# WRTnode.net
KiCad netlist of a schematic drawn in Altium Designer
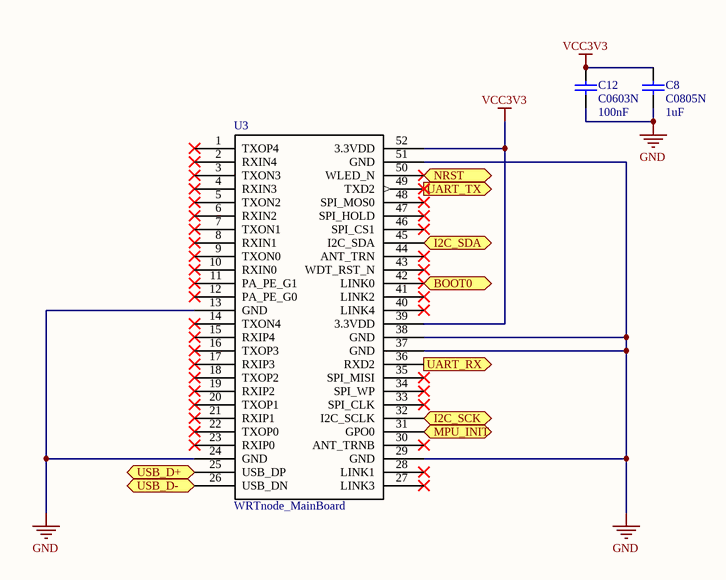
[diagram p0: WRTnode.SchDoc]

(export (version "E")
  (design (tool "Eeschema 10.0.6"))
  (components
    (comp (ref "C8")
      (value "C0805N")
      (footprint "C0805N")
      (description "Capacitor")
      (fields (field (name "ALTIUM_VALUE") "1uF") (field (name "PUBLISHER") "Altium Limited"))
      (libsource (lib "Miscellaneous Devices") (part "Cap"))
    )
    (comp (ref "C12")
      (value "C0603N")
      (footprint "C0603N")
      (description "Capacitor")
      (fields (field (name "ALTIUM_VALUE") "100nF") (field (name "PUBLISHER") "Altium Limited"))
      (libsource (lib "Miscellaneous Devices") (part "Cap"))
    )
    (comp (ref "U3")
      (value "WRTnode_MainBoard")
      (footprint "schumyhao's_IC:WRTnode_MainBoard_DIP26*2")
      (libsource (lib "schumyhao's_IC") (part "WRTnode_MainBoard"))
    )
  )
  (nets
    (net (code "1") (name "/BOOT0") (class "Default")
      (node (ref "U3") (pin "42") (pinfunction "LINK0_42") (pintype "passive+no_connect"))
    )
    (net (code "2") (name "/I2C_SCK") (class "Default")
      (node (ref "U3") (pin "32") (pinfunction "I2C_SCLK_32") (pintype "passive"))
    )
    (net (code "3") (name "/I2C_SDA") (class "Default")
      (node (ref "U3") (pin "45") (pinfunction "I2C_SDA_45") (pintype "passive"))
    )
    (net (code "4") (name "/MPU_INIT") (class "Default")
      (node (ref "U3") (pin "31") (pinfunction "GPO0_31") (pintype "passive"))
    )
    (net (code "5") (name "/NRST") (class "Default")
      (node (ref "U3") (pin "50") (pinfunction "WLED_N_50") (pintype "passive+no_connect"))
    )
    (net (code "6") (name "/UART_RX") (class "Default")
      (node (ref "U3") (pin "36") (pinfunction "RXD2_36") (pintype "passive"))
    )
    (net (code "7") (name "/UART_TX") (class "Default")
      (node (ref "U3") (pin "49") (pinfunction "TXD2_49") (pintype "output+no_connect"))
    )
    (net (code "8") (name "/USB_D+") (class "Default")
      (node (ref "U3") (pin "25") (pinfunction "USB_DP_25") (pintype "passive"))
    )
    (net (code "9") (name "/USB_D-") (class "Default")
      (node (ref "U3") (pin "26") (pinfunction "USB_DN_26") (pintype "passive"))
    )
    (net (code "10") (name "GND") (class "Default")
      (node (ref "C12") (pin "1") (pinfunction "1_1") (pintype "passive"))
      (node (ref "C8") (pin "1") (pinfunction "1_1") (pintype "passive"))
      (node (ref "U3") (pin "13") (pinfunction "GND_13") (pintype "passive"))
      (node (ref "U3") (pin "24") (pinfunction "GND_24") (pintype "passive"))
      (node (ref "U3") (pin "29") (pinfunction "GND_29") (pintype "passive"))
      (node (ref "U3") (pin "37") (pinfunction "GND_37") (pintype "passive"))
      (node (ref "U3") (pin "38") (pinfunction "GND_38") (pintype "passive"))
      (node (ref "U3") (pin "51") (pinfunction "GND_51") (pintype "passive"))
    )
    (net (code "11") (name "VCC3V3") (class "Default")
      (node (ref "C12") (pin "2") (pinfunction "2_2") (pintype "passive"))
      (node (ref "C8") (pin "2") (pinfunction "2_2") (pintype "passive"))
      (node (ref "U3") (pin "39") (pinfunction "3.3VDD_39") (pintype "passive"))
      (node (ref "U3") (pin "52") (pinfunction "3.3VDD_52") (pintype "passive"))
    )
    (net (code "12") (name "unconnected-(U3-ANT_TRN-Pad44)") (class "Default")
      (node (ref "U3") (pin "44") (pinfunction "ANT_TRN_44") (pintype "passive+no_connect"))
    )
    (net (code "13") (name "unconnected-(U3-ANT_TRNB-Pad30)") (class "Default")
      (node (ref "U3") (pin "30") (pinfunction "ANT_TRNB_30") (pintype "passive+no_connect"))
    )
    (net (code "14") (name "unconnected-(U3-LINK1-Pad28)") (class "Default")
      (node (ref "U3") (pin "28") (pinfunction "LINK1_28") (pintype "passive+no_connect"))
    )
    (net (code "15") (name "unconnected-(U3-LINK2-Pad41)") (class "Default")
      (node (ref "U3") (pin "41") (pinfunction "LINK2_41") (pintype "passive+no_connect"))
    )
    (net (code "16") (name "unconnected-(U3-LINK3-Pad27)") (class "Default")
      (node (ref "U3") (pin "27") (pinfunction "LINK3_27") (pintype "passive+no_connect"))
    )
    (net (code "17") (name "unconnected-(U3-LINK4-Pad40)") (class "Default")
      (node (ref "U3") (pin "40") (pinfunction "LINK4_40") (pintype "passive+no_connect"))
    )
    (net (code "18") (name "unconnected-(U3-PA_PE_G0-Pad12)") (class "Default")
      (node (ref "U3") (pin "12") (pinfunction "PA_PE_G0_12") (pintype "passive+no_connect"))
    )
    (net (code "19") (name "unconnected-(U3-PA_PE_G1-Pad11)") (class "Default")
      (node (ref "U3") (pin "11") (pinfunction "PA_PE_G1_11") (pintype "passive+no_connect"))
    )
    (net (code "20") (name "unconnected-(U3-RXIN0-Pad10)") (class "Default")
      (node (ref "U3") (pin "10") (pinfunction "RXIN0_10") (pintype "passive+no_connect"))
    )
    (net (code "21") (name "unconnected-(U3-RXIN1-Pad8)") (class "Default")
      (node (ref "U3") (pin "8") (pinfunction "RXIN1_8") (pintype "passive+no_connect"))
    )
    (net (code "22") (name "unconnected-(U3-RXIN2-Pad6)") (class "Default")
      (node (ref "U3") (pin "6") (pinfunction "RXIN2_6") (pintype "passive+no_connect"))
    )
    (net (code "23") (name "unconnected-(U3-RXIN3-Pad4)") (class "Default")
      (node (ref "U3") (pin "4") (pinfunction "RXIN3_4") (pintype "passive+no_connect"))
    )
    (net (code "24") (name "unconnected-(U3-RXIN4-Pad2)") (class "Default")
      (node (ref "U3") (pin "2") (pinfunction "RXIN4_2") (pintype "passive+no_connect"))
    )
    (net (code "25") (name "unconnected-(U3-RXIP0-Pad23)") (class "Default")
      (node (ref "U3") (pin "23") (pinfunction "RXIP0_23") (pintype "passive+no_connect"))
    )
    (net (code "26") (name "unconnected-(U3-RXIP1-Pad21)") (class "Default")
      (node (ref "U3") (pin "21") (pinfunction "RXIP1_21") (pintype "passive+no_connect"))
    )
    (net (code "27") (name "unconnected-(U3-RXIP2-Pad19)") (class "Default")
      (node (ref "U3") (pin "19") (pinfunction "RXIP2_19") (pintype "passive+no_connect"))
    )
    (net (code "28") (name "unconnected-(U3-RXIP3-Pad17)") (class "Default")
      (node (ref "U3") (pin "17") (pinfunction "RXIP3_17") (pintype "passive+no_connect"))
    )
    (net (code "29") (name "unconnected-(U3-RXIP4-Pad15)") (class "Default")
      (node (ref "U3") (pin "15") (pinfunction "RXIP4_15") (pintype "passive+no_connect"))
    )
    (net (code "30") (name "unconnected-(U3-SPI_CLK-Pad33)") (class "Default")
      (node (ref "U3") (pin "33") (pinfunction "SPI_CLK_33") (pintype "passive+no_connect"))
    )
    (net (code "31") (name "unconnected-(U3-SPI_CS1-Pad46)") (class "Default")
      (node (ref "U3") (pin "46") (pinfunction "SPI_CS1_46") (pintype "passive+no_connect"))
    )
    (net (code "32") (name "unconnected-(U3-SPI_HOLD-Pad47)") (class "Default")
      (node (ref "U3") (pin "47") (pinfunction "SPI_HOLD_47") (pintype "passive+no_connect"))
    )
    (net (code "33") (name "unconnected-(U3-SPI_MISI-Pad35)") (class "Default")
      (node (ref "U3") (pin "35") (pinfunction "SPI_MISI_35") (pintype "passive+no_connect"))
    )
    (net (code "34") (name "unconnected-(U3-SPI_MOS0-Pad48)") (class "Default")
      (node (ref "U3") (pin "48") (pinfunction "SPI_MOS0_48") (pintype "passive+no_connect"))
    )
    (net (code "35") (name "unconnected-(U3-SPI_WP-Pad34)") (class "Default")
      (node (ref "U3") (pin "34") (pinfunction "SPI_WP_34") (pintype "passive+no_connect"))
    )
    (net (code "36") (name "unconnected-(U3-TXON0-Pad9)") (class "Default")
      (node (ref "U3") (pin "9") (pinfunction "TXON0_9") (pintype "passive+no_connect"))
    )
    (net (code "37") (name "unconnected-(U3-TXON1-Pad7)") (class "Default")
      (node (ref "U3") (pin "7") (pinfunction "TXON1_7") (pintype "passive+no_connect"))
    )
    (net (code "38") (name "unconnected-(U3-TXON2-Pad5)") (class "Default")
      (node (ref "U3") (pin "5") (pinfunction "TXON2_5") (pintype "passive+no_connect"))
    )
    (net (code "39") (name "unconnected-(U3-TXON3-Pad3)") (class "Default")
      (node (ref "U3") (pin "3") (pinfunction "TXON3_3") (pintype "passive+no_connect"))
    )
    (net (code "40") (name "unconnected-(U3-TXON4-Pad14)") (class "Default")
      (node (ref "U3") (pin "14") (pinfunction "TXON4_14") (pintype "passive+no_connect"))
    )
    (net (code "41") (name "unconnected-(U3-TXOP0-Pad22)") (class "Default")
      (node (ref "U3") (pin "22") (pinfunction "TXOP0_22") (pintype "passive+no_connect"))
    )
    (net (code "42") (name "unconnected-(U3-TXOP1-Pad20)") (class "Default")
      (node (ref "U3") (pin "20") (pinfunction "TXOP1_20") (pintype "passive+no_connect"))
    )
    (net (code "43") (name "unconnected-(U3-TXOP2-Pad18)") (class "Default")
      (node (ref "U3") (pin "18") (pinfunction "TXOP2_18") (pintype "passive+no_connect"))
    )
    (net (code "44") (name "unconnected-(U3-TXOP3-Pad16)") (class "Default")
      (node (ref "U3") (pin "16") (pinfunction "TXOP3_16") (pintype "passive+no_connect"))
    )
    (net (code "45") (name "unconnected-(U3-TXOP4-Pad1)") (class "Default")
      (node (ref "U3") (pin "1") (pinfunction "TXOP4_1") (pintype "passive+no_connect"))
    )
    (net (code "46") (name "unconnected-(U3-WDT_RST_N-Pad43)") (class "Default")
      (node (ref "U3") (pin "43") (pinfunction "WDT_RST_N_43") (pintype "passive+no_connect"))
    )
  )
)
